# Power_board_2024-08-19.net
KiCad netlist of a schematic drawn in Altium Designer
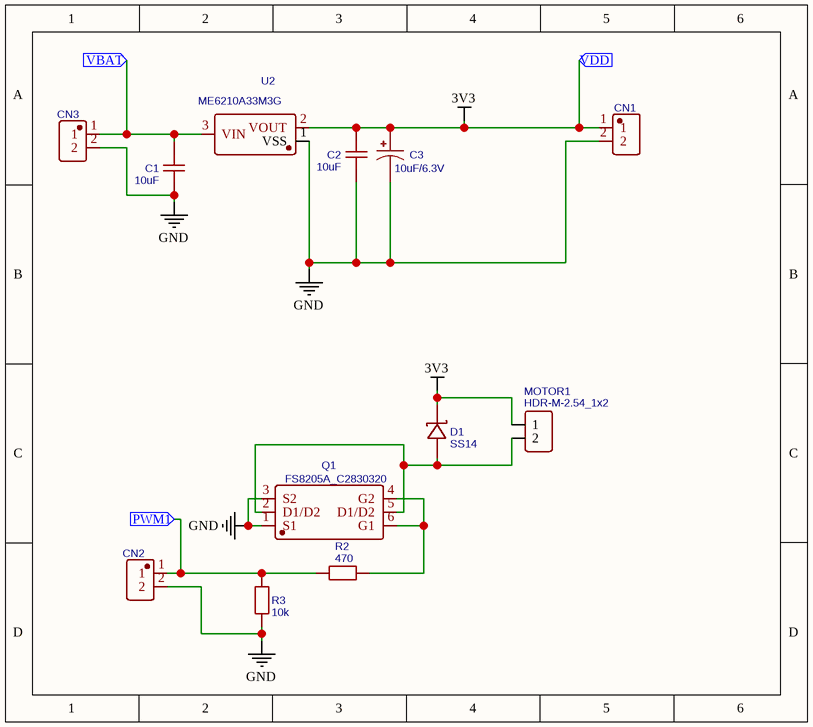
[diagram p0: Power_board_2024-08-19.schdoc]

(export (version "E")
  (design (tool "Eeschema 10.0.6"))
  (components
    (comp (ref "C1")
      (value "10uF")
      (fields (field (name "CONTRIBUTOR") "LCEDA_Lib"))
      (libsource (lib "altium-import") (part "root_1_10uF_"))
    )
    (comp (ref "C2")
      (value "10uF")
      (fields (field (name "CONTRIBUTOR") "LCEDA_Lib"))
      (libsource (lib "altium-import") (part "root_1_10uF_"))
    )
    (comp (ref "C3")
      (value "10uF/6.3V")
      (fields (field (name "CONTRIBUTOR") "LCEDA_Lib"))
      (libsource (lib "altium-import") (part "root_3_10uF/6.3V_"))
    )
    (comp (ref "CN1")
      (value "KH-1.27FH-1X2P-H4.3")
      (fields (field (name "MANUFACTURER") "kinghelm(金航标)") (field (name "CONTRIBUTOR") "LCSC"))
      (libsource (lib "altium-import") (part "root_0_KH-1.27FH-1X2P-H4.3_"))
    )
    (comp (ref "CN2")
      (value "KH-1.27FH-1X2P-H4.3")
      (fields (field (name "MANUFACTURER") "kinghelm(金航标)") (field (name "CONTRIBUTOR") "LCSC"))
      (libsource (lib "") (part "root_0_KH-1.27FH-1X2P-H4.3__1"))
    )
    (comp (ref "CN3")
      (value "KH-1.27FH-1X2P-H4.3")
      (fields (field (name "MANUFACTURER") "kinghelm(金航标)") (field (name "CONTRIBUTOR") "LCSC"))
      (libsource (lib "") (part "root_0_KH-1.27FH-1X2P-H4.3__1"))
    )
    (comp (ref "D1")
      (value "SS14")
      (fields (field (name "BOM_SUPPLIER PART") "C2480"))
      (libsource (lib "altium-import") (part "root_3_SS14_"))
    )
    (comp (ref "MOTOR1")
      (value "HDR-M-2.54_1x2")
      (fields (field (name "BOM_SUPPLIER PART") "C124375") (field (name "CONTRIBUTOR") "LCEDA_Lib"))
      (libsource (lib "altium-import") (part "root_0_HDR-M-2.54_1x2_"))
    )
    (comp (ref "Q1")
      (value "FS8205A_C2830320")
      (fields
        (field (name "BOM_SUPPLIER PART") "C2830320")
        (field (name "BOM_MANUFACTURER PART") "FS8205A")
        (field (name "CONTRIBUTOR") "LCSC")
      )
      (libsource (lib "altium-import") (part "root_2_FS8205A_C2830320_"))
    )
    (comp (ref "R2")
      (value "470")
      (fields (field (name "CONTRIBUTOR") "LCEDA_Lib"))
      (libsource (lib "altium-import") (part "root_0_470_"))
    )
    (comp (ref "R3")
      (value "10k")
      (fields (field (name "CONTRIBUTOR") "LCEDA_Lib"))
      (libsource (lib "altium-import") (part "root_1_10k_"))
    )
    (comp (ref "U2")
      (value "ME6210A33M3G")
      (fields (field (name "MANUFACTURER") "MICRONE(南京微盟)") (field (name "CONTRIBUTOR") "LCSC"))
      (libsource (lib "altium-import") (part "root_0_ME6210A33M3G_"))
    )
  )
  (nets
    (net (code "1") (name "/PWM1") (class "Default")
      (node (ref "CN2") (pin "1") (pinfunction "1_1") (pintype "passive"))
      (node (ref "R2") (pin "1") (pinfunction "1_1") (pintype "passive"))
      (node (ref "R3") (pin "2") (pinfunction "2_2") (pintype "passive"))
    )
    (net (code "2") (name "/VBAT") (class "Default")
      (node (ref "C1") (pin "2") (pinfunction "2_2") (pintype "passive"))
      (node (ref "CN3") (pin "1") (pinfunction "1_1") (pintype "passive"))
      (node (ref "U2") (pin "3") (pinfunction "VIN_3") (pintype "passive"))
    )
    (net (code "3") (name "3V3") (class "Default")
      (node (ref "C2") (pin "2") (pinfunction "2_2") (pintype "passive"))
      (node (ref "C3") (pin "1") (pinfunction "1_1") (pintype "passive"))
      (node (ref "CN1") (pin "1") (pinfunction "1_1") (pintype "passive"))
      (node (ref "D1") (pin "1") (pinfunction "K_1") (pintype "passive"))
      (node (ref "MOTOR1") (pin "1") (pinfunction "1_1") (pintype "passive"))
      (node (ref "U2") (pin "2") (pinfunction "VOUT_2") (pintype "passive"))
    )
    (net (code "4") (name "GND") (class "Default")
      (node (ref "C1") (pin "1") (pinfunction "1_1") (pintype "passive"))
      (node (ref "C2") (pin "1") (pinfunction "1_1") (pintype "passive"))
      (node (ref "C3") (pin "2") (pinfunction "2_2") (pintype "passive"))
      (node (ref "CN1") (pin "2") (pinfunction "2_2") (pintype "passive"))
      (node (ref "CN2") (pin "2") (pinfunction "2_2") (pintype "passive"))
      (node (ref "CN3") (pin "2") (pinfunction "2_2") (pintype "passive"))
      (node (ref "Q1") (pin "1") (pinfunction "S1_1") (pintype "passive"))
      (node (ref "Q1") (pin "3") (pinfunction "S2_3") (pintype "passive"))
      (node (ref "R3") (pin "1") (pinfunction "1_1") (pintype "passive"))
      (node (ref "U2") (pin "1") (pinfunction "VSS_1") (pintype "passive"))
    )
    (net (code "5") (name "Net-(D1-A)") (class "Default")
      (node (ref "D1") (pin "2") (pinfunction "A_2") (pintype "passive"))
      (node (ref "MOTOR1") (pin "2") (pinfunction "2_2") (pintype "passive"))
      (node (ref "Q1") (pin "2") (pinfunction "D1/D2_2") (pintype "passive"))
      (node (ref "Q1") (pin "5") (pinfunction "D1/D2_5") (pintype "passive"))
    )
    (net (code "6") (name "Net-(Q1-G1)") (class "Default")
      (node (ref "Q1") (pin "4") (pinfunction "G2_4") (pintype "passive"))
      (node (ref "Q1") (pin "6") (pinfunction "G1_6") (pintype "passive"))
      (node (ref "R2") (pin "2") (pinfunction "2_2") (pintype "passive"))
    )
  )
)
